# E500.net
KiCad netlist of a schematic drawn in EAGLE
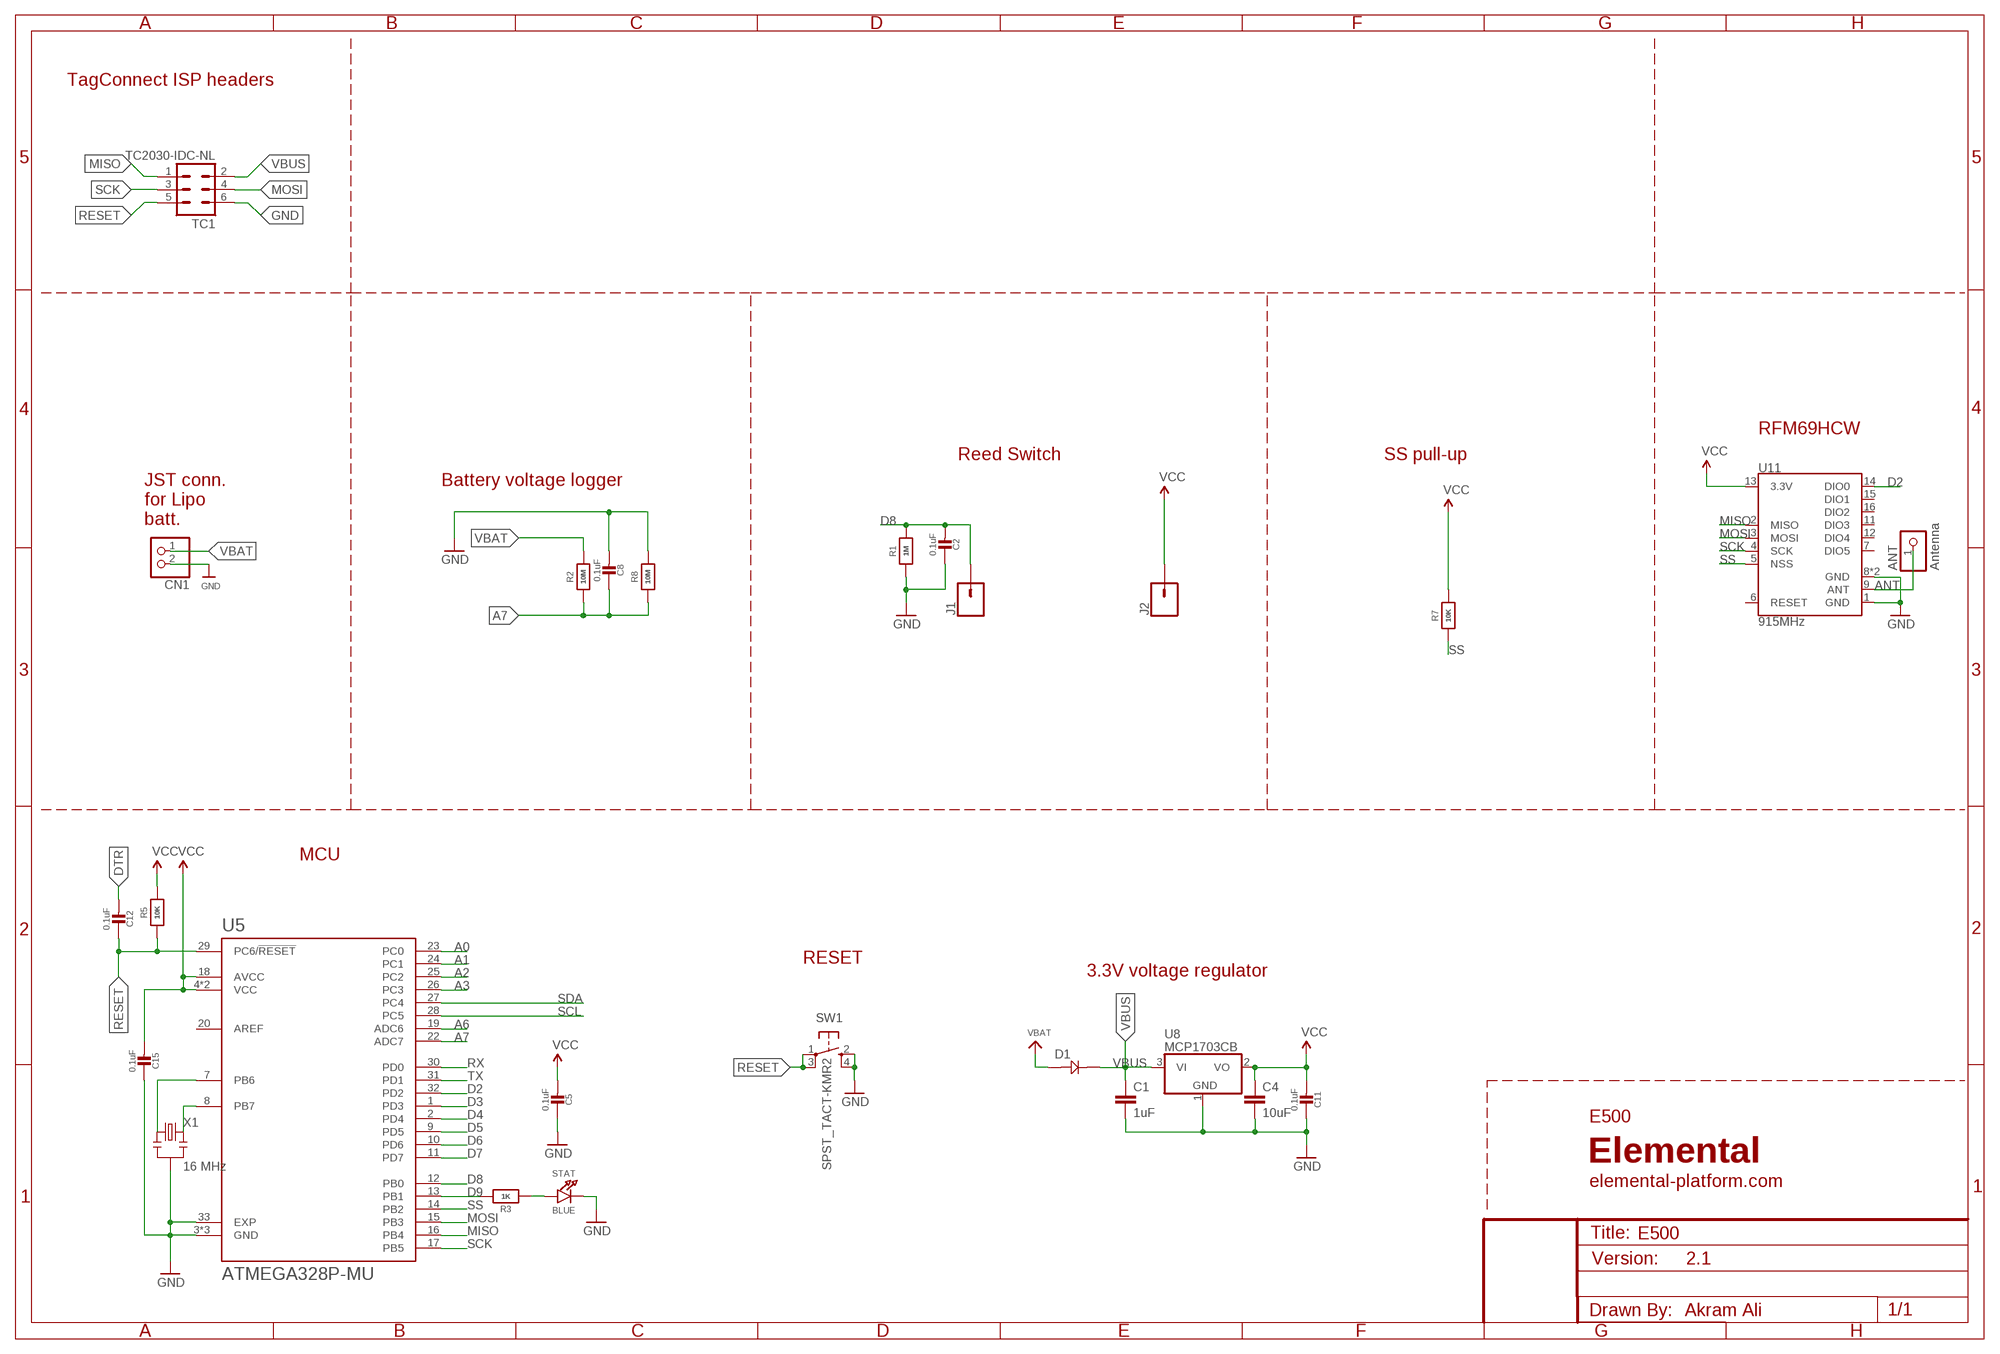
[diagram p0: schematic, sheet 1]

(export (version "E")
  (design (tool "Eeschema 10.0.6"))
  (components
    (comp (ref "ANT")
      (value "Antenna")
      (footprint "eagle-import:1X01-CLEANBIG")
      (fields (field (name "MPN") "Helical antenna"))
      (libsource (lib "eagle-import") (part "PINHD-1X1CB"))
    )
    (comp (ref "C1")
      (value "1uF")
      (footprint "eagle-import:0805")
      (fields (field (name "MPN") "CC0805ZRY5V8BB105"))
      (libsource (lib "eagle-import") (part "CAP0805"))
    )
    (comp (ref "C2")
      (value "0.1uF")
      (footprint "eagle-import:MICROBUILDER__0402MP")
      (fields (field (name "MPN") "GRM155R71C104KA88J"))
      (libsource (lib "eagle-import") (part "MICROBUILDER_CAP_CERAMIC_0402MP"))
    )
    (comp (ref "C4")
      (value "10uF")
      (footprint "eagle-import:0805")
      (fields (field (name "MPN") "CC0805KKX5R6BB106"))
      (libsource (lib "eagle-import") (part "CAP0805"))
    )
    (comp (ref "C5")
      (value "0.1uF")
      (footprint "eagle-import:MICROBUILDER__0402MP")
      (fields (field (name "MPN") "GRM155R71C104KA88J"))
      (libsource (lib "eagle-import") (part "MICROBUILDER_CAP_CERAMIC_0402MP"))
    )
    (comp (ref "C8")
      (value "0.1uF")
      (footprint "eagle-import:MICROBUILDER__0402MP")
      (fields (field (name "MPN") "GRM155R71C104KA88J"))
      (libsource (lib "eagle-import") (part "MICROBUILDER_CAP_CERAMIC_0402MP"))
    )
    (comp (ref "C11")
      (value "0.1uF")
      (footprint "eagle-import:MICROBUILDER__0402MP")
      (fields (field (name "MPN") "GRM155R71C104KA88J"))
      (libsource (lib "eagle-import") (part "MICROBUILDER_CAP_CERAMIC_0402MP"))
    )
    (comp (ref "C12")
      (value "0.1uF")
      (footprint "eagle-import:MICROBUILDER__0402MP")
      (fields (field (name "MPN") "GRM155R71C104KA88J"))
      (libsource (lib "eagle-import") (part "MICROBUILDER_CAP_CERAMIC_0402MP"))
    )
    (comp (ref "C15")
      (value "0.1uF")
      (footprint "eagle-import:MICROBUILDER__0402MP")
      (fields (field (name "MPN") "GRM155R71C104KA88J"))
      (libsource (lib "eagle-import") (part "MICROBUILDER_CAP_CERAMIC_0402MP"))
    )
    (comp (ref "CN1")
      (value "JST_2PIN-SMT-RA")
      (footprint "eagle-import:JST-PH-2-SMT-RA")
      (libsource (lib "eagle-import") (part "JST_2PIN-SMT-RA"))
    )
    (comp (ref "D1")
      (value "DIODE_SCHOTTKY0805-RES")
      (footprint "eagle-import:0805")
      (libsource (lib "eagle-import") (part "DIODE_SCHOTTKY0805-RES"))
    )
    (comp (ref "J1")
      (value "CONN_01")
      (footprint "eagle-import:1X01")
      (libsource (lib "eagle-import") (part "CONN_01"))
    )
    (comp (ref "J2")
      (value "CONN_01")
      (footprint "eagle-import:1X01")
      (libsource (lib "eagle-import") (part "CONN_01"))
    )
    (comp (ref "R1")
      (value "1M")
      (footprint "eagle-import:MICROBUILDER__0402MP")
      (fields (field (name "MPN") "RC0402JR-0710KL"))
      (libsource (lib "eagle-import") (part "MICROBUILDER_RESISTOR_0402MP"))
    )
    (comp (ref "R2")
      (value "10M")
      (footprint "eagle-import:MICROBUILDER__0402MP")
      (fields (field (name "MPN") "RC0402JR-0710KL"))
      (libsource (lib "eagle-import") (part "MICROBUILDER_RESISTOR_0402MP"))
    )
    (comp (ref "R3")
      (value "1K")
      (footprint "eagle-import:MICROBUILDER__0402MP")
      (fields (field (name "MPN") "RC0402JR-0710KL"))
      (libsource (lib "eagle-import") (part "MICROBUILDER_RESISTOR_0402MP"))
    )
    (comp (ref "R5")
      (value "10K")
      (footprint "eagle-import:MICROBUILDER__0402MP")
      (fields (field (name "MPN") "RC0402JR-0710KL"))
      (libsource (lib "eagle-import") (part "MICROBUILDER_RESISTOR_0402MP"))
    )
    (comp (ref "R7")
      (value "10K")
      (footprint "eagle-import:MICROBUILDER__0402MP")
      (fields (field (name "MPN") "RC0402JR-0710KL"))
      (libsource (lib "eagle-import") (part "MICROBUILDER_RESISTOR_0402MP"))
    )
    (comp (ref "R8")
      (value "10M")
      (footprint "eagle-import:MICROBUILDER__0402MP")
      (fields (field (name "MPN") "RC0402JR-0710KL"))
      (libsource (lib "eagle-import") (part "MICROBUILDER_RESISTOR_0402MP"))
    )
    (comp (ref "STAT")
      (value "BLUE")
      (footprint "eagle-import:CHIPLED_0805_NOOUTLINE")
      (libsource (lib "eagle-import") (part "LED0805_NOOUTLINE"))
    )
    (comp (ref "SW1")
      (value "SPST_TACT-KMR2")
      (footprint "eagle-import:KMR2")
      (libsource (lib "eagle-import") (part "SPST_TACT-KMR2"))
    )
    (comp (ref "TC1")
      (value "TC2030-IDC-NL")
      (footprint "eagle-import:TC2030-IDC-NL")
      (libsource (lib "eagle-import") (part "TC2030-IDC-NL"))
    )
    (comp (ref "U5")
      (value "ATMEGA328P-MU")
      (footprint "eagle-import:QFN50P500X500X100-33N")
      (fields (field (name "MF") "Atmel"))
      (libsource (lib "eagle-import") (part "ATMEGA328P-MU"))
    )
    (comp (ref "U8")
      (value "MCP1703CB")
      (footprint "eagle-import:SOT23")
      (fields (field (name "MPN") "MCP1703T-3302E/CB"))
      (libsource (lib "eagle-import") (part "MCP1703CB"))
    )
    (comp (ref "U11")
      (value "915MHz")
      (footprint "eagle-import:RFM69HCW-XXXS2")
      (fields (field (name "MPN") "RFM69HCW"))
      (libsource (lib "eagle-import") (part "RFM69HCW-915"))
    )
    (comp (ref "X1")
      (value "16 MHz")
      (footprint "eagle-import:RESONATOR-SMD")
      (fields (field (name "MPN") "CSTCE16M0V53-R0"))
      (libsource (lib "eagle-import") (part "RESONATORSMD"))
    )
  )
  (nets
    (net (code "1") (name "/A0") (class "Default")
      (node (ref "U5") (pin "23") (pinfunction "PC0_23") (pintype "bidirectional"))
    )
    (net (code "2") (name "/A1") (class "Default")
      (node (ref "U5") (pin "24") (pinfunction "PC1_24") (pintype "bidirectional"))
    )
    (net (code "3") (name "/A2") (class "Default")
      (node (ref "U5") (pin "25") (pinfunction "PC2_25") (pintype "bidirectional"))
    )
    (net (code "4") (name "/A3") (class "Default")
      (node (ref "U5") (pin "26") (pinfunction "PC3_26") (pintype "bidirectional"))
    )
    (net (code "5") (name "/A6") (class "Default")
      (node (ref "U5") (pin "19") (pinfunction "ADC6_19") (pintype "bidirectional"))
    )
    (net (code "6") (name "/ANT") (class "Default")
      (node (ref "ANT") (pin "1") (pinfunction "1_1") (pintype "passive"))
      (node (ref "U11") (pin "9") (pinfunction "ANT_9") (pintype "passive"))
    )
    (net (code "7") (name "/D2") (class "Default")
      (node (ref "U11") (pin "14") (pinfunction "DIO0_14") (pintype "bidirectional"))
      (node (ref "U5") (pin "32") (pinfunction "PD2_32") (pintype "bidirectional"))
    )
    (net (code "8") (name "/D3") (class "Default")
      (node (ref "U5") (pin "1") (pinfunction "PD3_1") (pintype "bidirectional"))
    )
    (net (code "9") (name "/D4") (class "Default")
      (node (ref "U5") (pin "2") (pinfunction "PD4_2") (pintype "bidirectional"))
    )
    (net (code "10") (name "/D5") (class "Default")
      (node (ref "U5") (pin "9") (pinfunction "PD5_9") (pintype "bidirectional"))
    )
    (net (code "11") (name "/D6") (class "Default")
      (node (ref "U5") (pin "10") (pinfunction "PD6_10") (pintype "bidirectional"))
    )
    (net (code "12") (name "/D7") (class "Default")
      (node (ref "U5") (pin "11") (pinfunction "PD7_11") (pintype "bidirectional"))
    )
    (net (code "13") (name "/D8") (class "Default")
      (node (ref "C2") (pin "2") (pinfunction "2_2") (pintype "passive"))
      (node (ref "J1") (pin "1") (pinfunction "1_1") (pintype "passive"))
      (node (ref "R1") (pin "2") (pinfunction "2_2") (pintype "passive"))
      (node (ref "U5") (pin "12") (pinfunction "PB0_12") (pintype "bidirectional"))
    )
    (net (code "14") (name "/D9") (class "Default")
      (node (ref "R3") (pin "2") (pinfunction "2_2") (pintype "passive"))
      (node (ref "U5") (pin "13") (pinfunction "PB1_13") (pintype "bidirectional"))
    )
    (net (code "15") (name "/RX") (class "Default")
      (node (ref "U5") (pin "30") (pinfunction "PD0_30") (pintype "bidirectional"))
    )
    (net (code "16") (name "/SCL") (class "Default")
      (node (ref "U5") (pin "28") (pinfunction "PC5_28") (pintype "bidirectional"))
    )
    (net (code "17") (name "/SDA") (class "Default")
      (node (ref "U5") (pin "27") (pinfunction "PC4_27") (pintype "bidirectional"))
    )
    (net (code "18") (name "/SS") (class "Default")
      (node (ref "R7") (pin "1") (pinfunction "1_1") (pintype "passive"))
      (node (ref "U11") (pin "5") (pinfunction "NSS_5") (pintype "input"))
      (node (ref "U5") (pin "14") (pinfunction "PB2_14") (pintype "bidirectional"))
    )
    (net (code "19") (name "/TX") (class "Default")
      (node (ref "U5") (pin "31") (pinfunction "PD1_31") (pintype "bidirectional"))
    )
    (net (code "20") (name "A7") (class "Default")
      (node (ref "C8") (pin "1") (pinfunction "1_1") (pintype "passive"))
      (node (ref "R2") (pin "1") (pinfunction "1_1") (pintype "passive"))
      (node (ref "R8") (pin "1") (pinfunction "1_1") (pintype "passive"))
      (node (ref "U5") (pin "22") (pinfunction "ADC7_22") (pintype "bidirectional"))
    )
    (net (code "21") (name "DTR") (class "Default")
      (node (ref "C12") (pin "2") (pinfunction "2_2") (pintype "passive"))
    )
    (net (code "22") (name "GND") (class "Default")
      (node (ref "C1") (pin "2") (pinfunction "2_2") (pintype "passive"))
      (node (ref "C11") (pin "1") (pinfunction "1_1") (pintype "passive"))
      (node (ref "C15") (pin "1") (pinfunction "1_1") (pintype "passive"))
      (node (ref "C2") (pin "1") (pinfunction "1_1") (pintype "passive"))
      (node (ref "C4") (pin "2") (pinfunction "2_2") (pintype "passive"))
      (node (ref "C5") (pin "1") (pinfunction "1_1") (pintype "passive"))
      (node (ref "C8") (pin "2") (pinfunction "2_2") (pintype "passive"))
      (node (ref "CN1") (pin "2") (pinfunction "1_2") (pintype "passive"))
      (node (ref "R1") (pin "1") (pinfunction "1_1") (pintype "passive"))
      (node (ref "R8") (pin "2") (pinfunction "2_2") (pintype "passive"))
      (node (ref "STAT") (pin "C") (pinfunction "C_C") (pintype "passive"))
      (node (ref "SW1") (pin "2") (pinfunction "S_2") (pintype "passive"))
      (node (ref "SW1") (pin "4") (pinfunction "S1_4") (pintype "passive"))
      (node (ref "TC1") (pin "6") (pinfunction "6_6") (pintype "passive"))
      (node (ref "U11") (pin "1") (pinfunction "GND_1") (pintype "power_in"))
      (node (ref "U11") (pin "10") (pinfunction "GND_10") (pintype "power_in"))
      (node (ref "U11") (pin "8") (pinfunction "GND_8") (pintype "power_in"))
      (node (ref "U5") (pin "21") (pinfunction "GND_21") (pintype "power_in"))
      (node (ref "U5") (pin "3") (pinfunction "GND_3") (pintype "power_in"))
      (node (ref "U5") (pin "33") (pinfunction "EXP_33") (pintype "power_in"))
      (node (ref "U5") (pin "5") (pinfunction "GND_5") (pintype "power_in"))
      (node (ref "U8") (pin "1") (pinfunction "GND_1") (pintype "passive"))
      (node (ref "X1") (pin "2") (pinfunction "2_2") (pintype "passive"))
    )
    (net (code "23") (name "MISO") (class "Default")
      (node (ref "TC1") (pin "1") (pinfunction "1_1") (pintype "passive"))
      (node (ref "U11") (pin "2") (pinfunction "MISO_2") (pintype "bidirectional"))
      (node (ref "U5") (pin "16") (pinfunction "PB4_16") (pintype "bidirectional"))
    )
    (net (code "24") (name "MOSI") (class "Default")
      (node (ref "TC1") (pin "4") (pinfunction "4_4") (pintype "passive"))
      (node (ref "U11") (pin "3") (pinfunction "MOSI_3") (pintype "input"))
      (node (ref "U5") (pin "15") (pinfunction "PB3_15") (pintype "bidirectional"))
    )
    (net (code "25") (name "Net-(R3-Pad1)") (class "Default")
      (node (ref "R3") (pin "1") (pinfunction "1_1") (pintype "passive"))
      (node (ref "STAT") (pin "A") (pinfunction "A_A") (pintype "passive"))
    )
    (net (code "26") (name "Net-(U5-PB6)") (class "Default")
      (node (ref "U5") (pin "7") (pinfunction "PB6_7") (pintype "bidirectional"))
      (node (ref "X1") (pin "1") (pinfunction "1_1") (pintype "passive"))
    )
    (net (code "27") (name "Net-(U5-PB7)") (class "Default")
      (node (ref "U5") (pin "8") (pinfunction "PB7_8") (pintype "bidirectional"))
      (node (ref "X1") (pin "3") (pinfunction "3_3") (pintype "passive"))
    )
    (net (code "28") (name "RESET") (class "Default")
      (node (ref "C12") (pin "1") (pinfunction "1_1") (pintype "passive"))
      (node (ref "R5") (pin "1") (pinfunction "1_1") (pintype "passive"))
      (node (ref "SW1") (pin "1") (pinfunction "P_1") (pintype "passive"))
      (node (ref "SW1") (pin "3") (pinfunction "P1_3") (pintype "passive"))
      (node (ref "TC1") (pin "5") (pinfunction "5_5") (pintype "passive"))
      (node (ref "U5") (pin "29") (pinfunction "PC6/~{RESET}_29") (pintype "bidirectional"))
    )
    (net (code "29") (name "SCK") (class "Default")
      (node (ref "TC1") (pin "3") (pinfunction "3_3") (pintype "passive"))
      (node (ref "U11") (pin "4") (pinfunction "SCK_4") (pintype "input"))
      (node (ref "U5") (pin "17") (pinfunction "PB5_17") (pintype "bidirectional"))
    )
    (net (code "30") (name "VBAT") (class "Default")
      (node (ref "CN1") (pin "1") (pinfunction "2_1") (pintype "passive"))
      (node (ref "D1") (pin "1") (pinfunction "1_1") (pintype "passive"))
      (node (ref "R2") (pin "2") (pinfunction "2_2") (pintype "passive"))
    )
    (net (code "31") (name "VBUS") (class "Default")
      (node (ref "C1") (pin "1") (pinfunction "1_1") (pintype "passive"))
      (node (ref "D1") (pin "2") (pinfunction "2_2") (pintype "passive"))
      (node (ref "TC1") (pin "2") (pinfunction "2_2") (pintype "passive"))
      (node (ref "U8") (pin "3") (pinfunction "VI_3") (pintype "input"))
    )
    (net (code "32") (name "VCC") (class "Default")
      (node (ref "C11") (pin "2") (pinfunction "2_2") (pintype "passive"))
      (node (ref "C15") (pin "2") (pinfunction "2_2") (pintype "passive"))
      (node (ref "C4") (pin "1") (pinfunction "1_1") (pintype "passive"))
      (node (ref "C5") (pin "2") (pinfunction "2_2") (pintype "passive"))
      (node (ref "J2") (pin "1") (pinfunction "1_1") (pintype "passive"))
      (node (ref "R5") (pin "2") (pinfunction "2_2") (pintype "passive"))
      (node (ref "R7") (pin "2") (pinfunction "2_2") (pintype "passive"))
      (node (ref "U11") (pin "13") (pinfunction "3.3V_13") (pintype "power_in"))
      (node (ref "U5") (pin "18") (pinfunction "AVCC_18") (pintype "power_in"))
      (node (ref "U5") (pin "4") (pinfunction "VCC_4") (pintype "power_in"))
      (node (ref "U5") (pin "6") (pinfunction "VCC_6") (pintype "power_in"))
      (node (ref "U8") (pin "2") (pinfunction "VO_2") (pintype "passive"))
    )
    (net (code "33") (name "unconnected-(U5-AREF-Pad20)") (class "Default")
      (node (ref "U5") (pin "20") (pinfunction "AREF_20") (pintype "input"))
    )
    (net (code "34") (name "unconnected-(U11-DIO1-Pad15)") (class "Default")
      (node (ref "U11") (pin "15") (pinfunction "DIO1_15") (pintype "bidirectional"))
    )
    (net (code "35") (name "unconnected-(U11-DIO2-Pad16)") (class "Default")
      (node (ref "U11") (pin "16") (pinfunction "DIO2_16") (pintype "bidirectional"))
    )
    (net (code "36") (name "unconnected-(U11-DIO3-Pad11)") (class "Default")
      (node (ref "U11") (pin "11") (pinfunction "DIO3_11") (pintype "bidirectional"))
    )
    (net (code "37") (name "unconnected-(U11-DIO4-Pad12)") (class "Default")
      (node (ref "U11") (pin "12") (pinfunction "DIO4_12") (pintype "bidirectional"))
    )
    (net (code "38") (name "unconnected-(U11-DIO5-Pad7)") (class "Default")
      (node (ref "U11") (pin "7") (pinfunction "DIO5_7") (pintype "bidirectional"))
    )
    (net (code "39") (name "unconnected-(U11-RESET-Pad6)") (class "Default")
      (node (ref "U11") (pin "6") (pinfunction "RESET_6") (pintype "input"))
    )
  )
)
